# i2c-servo.net
KiCad netlist of a schematic drawn in EAGLE
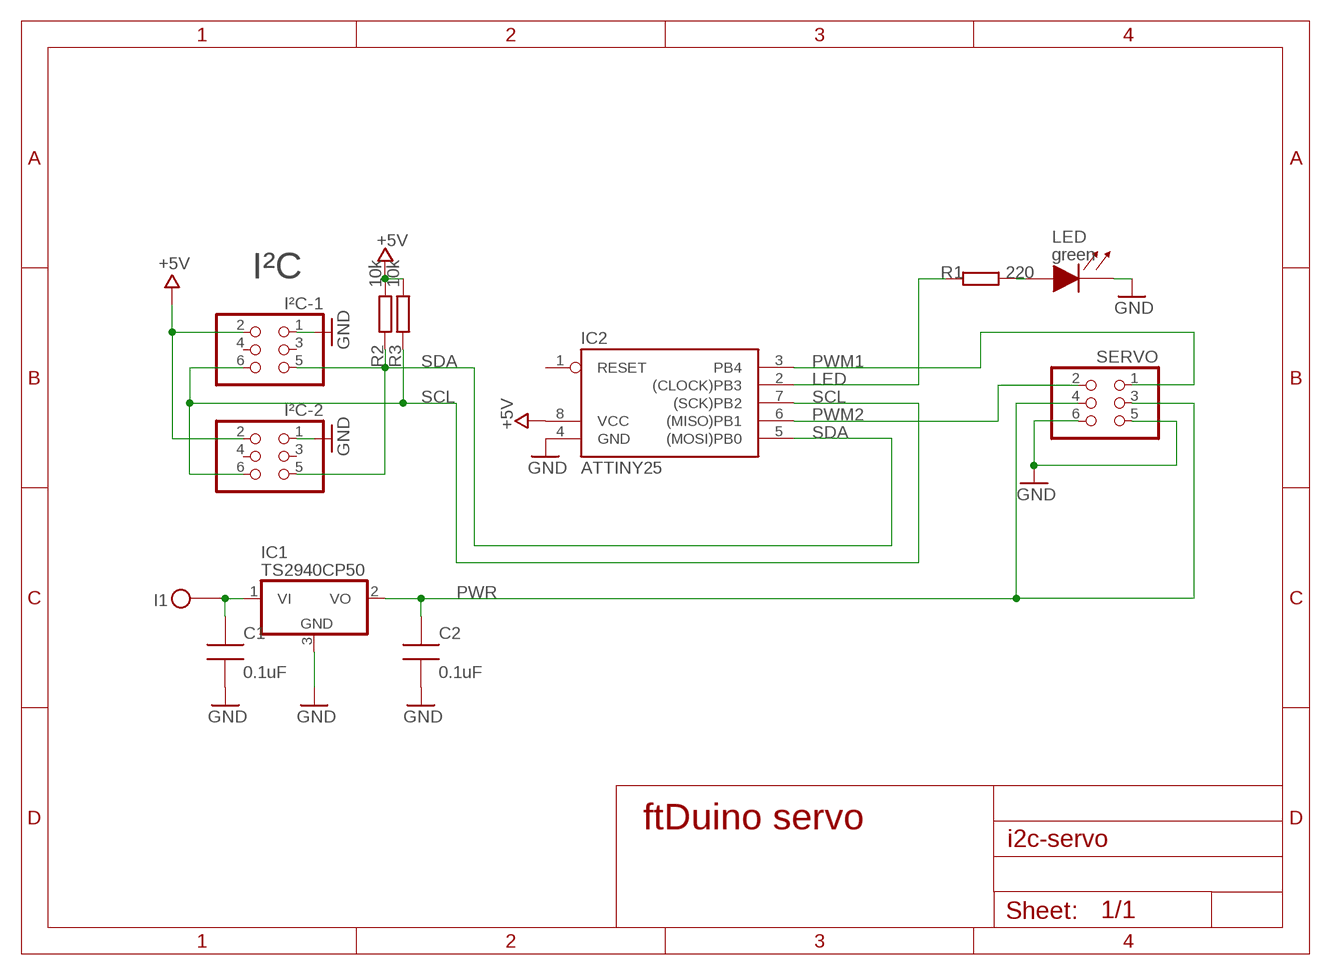
[diagram p0: schematic, sheet 1]

(export (version "E")
  (design (tool "Eeschema 10.0.6"))
  (components
    (comp (ref "C1")
      (value "0.1uF")
      (footprint "eagle-import:CAP0805-NP")
      (libsource (lib "eagle-import") (part "CAP0805-NP"))
    )
    (comp (ref "C2")
      (value "0.1uF")
      (footprint "eagle-import:CAP0805-NP")
      (libsource (lib "eagle-import") (part "CAP0805-NP"))
    )
    (comp (ref "H5")
      (value "I1")
      (footprint "eagle-import:FT-HUELSE")
      (libsource (lib "eagle-import") (part "FT-HUELSE"))
    )
    (comp (ref "IC1")
      (value "TS2940CP50")
      (footprint "eagle-import:TO252")
      (libsource (lib "eagle-import") (part "78DT05"))
    )
    (comp (ref "IC2")
      (value "ATTINY25")
      (footprint "eagle-import:SOIC8")
      (libsource (lib "eagle-import") (part "TINY22S"))
    )
    (comp (ref "I²C-1")
      (value "PINHD-2X3_2.54-SMD")
      (footprint "eagle-import:2X03SMD")
      (libsource (lib "eagle-import") (part "PINHD-2X3_2.54-SMD"))
    )
    (comp (ref "I²C-2")
      (value "PINHD-2X3_2.54-SMD")
      (footprint "eagle-import:2X03SMD")
      (libsource (lib "eagle-import") (part "PINHD-2X3_2.54-SMD"))
    )
    (comp (ref "LED")
      (value "green")
      (footprint "eagle-import:LED0805")
      (libsource (lib "eagle-import") (part "LED0805"))
    )
    (comp (ref "R1")
      (value "220")
      (footprint "eagle-import:M0805")
      (libsource (lib "eagle-import") (part "R-EU_M0805"))
    )
    (comp (ref "R2")
      (value "10k")
      (footprint "eagle-import:M0805")
      (libsource (lib "eagle-import") (part "resistor_R-EU_M0805"))
    )
    (comp (ref "R3")
      (value "10k")
      (footprint "eagle-import:M0805")
      (libsource (lib "eagle-import") (part "resistor_R-EU_M0805"))
    )
    (comp (ref "SERVO")
      (value "PINHD-2X3_2.54-SMD")
      (footprint "eagle-import:2X03SMD")
      (libsource (lib "eagle-import") (part "PINHD-2X3_2.54-SMD"))
    )
  )
  (nets
    (net (code "1") (name "+5V") (class "Default")
      (node (ref "IC2") (pin "8") (pinfunction "VCC_8") (pintype "power_in"))
      (node (ref "I²C-1") (pin "2") (pinfunction "2_2") (pintype "passive"))
      (node (ref "I²C-2") (pin "2") (pinfunction "2_2") (pintype "passive"))
      (node (ref "R2") (pin "2") (pinfunction "2_2") (pintype "passive"))
      (node (ref "R3") (pin "2") (pinfunction "2_2") (pintype "passive"))
    )
    (net (code "2") (name "/LED") (class "Default")
      (node (ref "IC2") (pin "2") (pinfunction "(CLOCK)PB3_2") (pintype "bidirectional"))
      (node (ref "R1") (pin "1") (pinfunction "1_1") (pintype "passive"))
    )
    (net (code "3") (name "/PWM1") (class "Default")
      (node (ref "IC2") (pin "3") (pinfunction "PB4_3") (pintype "bidirectional"))
      (node (ref "SERVO") (pin "1") (pinfunction "1_1") (pintype "passive"))
    )
    (net (code "4") (name "/PWM2") (class "Default")
      (node (ref "IC2") (pin "6") (pinfunction "(MISO)PB1_6") (pintype "bidirectional"))
      (node (ref "SERVO") (pin "2") (pinfunction "2_2") (pintype "passive"))
    )
    (net (code "5") (name "/PWR") (class "Default")
      (node (ref "C2") (pin "1") (pinfunction "1_1") (pintype "passive"))
      (node (ref "IC1") (pin "2") (pinfunction "VO_2") (pintype "passive"))
      (node (ref "SERVO") (pin "3") (pinfunction "3_3") (pintype "passive"))
      (node (ref "SERVO") (pin "4") (pinfunction "4_4") (pintype "passive"))
    )
    (net (code "6") (name "/SCL") (class "Default")
      (node (ref "IC2") (pin "7") (pinfunction "(SCK)PB2_7") (pintype "bidirectional"))
      (node (ref "I²C-1") (pin "6") (pinfunction "6_6") (pintype "passive"))
      (node (ref "I²C-2") (pin "6") (pinfunction "6_6") (pintype "passive"))
      (node (ref "R3") (pin "1") (pinfunction "1_1") (pintype "passive"))
    )
    (net (code "7") (name "/SDA") (class "Default")
      (node (ref "IC2") (pin "5") (pinfunction "(MOSI)PB0_5") (pintype "bidirectional"))
      (node (ref "I²C-1") (pin "5") (pinfunction "5_5") (pintype "passive"))
      (node (ref "I²C-2") (pin "5") (pinfunction "5_5") (pintype "passive"))
      (node (ref "R2") (pin "1") (pinfunction "1_1") (pintype "passive"))
    )
    (net (code "8") (name "GND") (class "Default")
      (node (ref "C1") (pin "2") (pinfunction "2_2") (pintype "passive"))
      (node (ref "C2") (pin "2") (pinfunction "2_2") (pintype "passive"))
      (node (ref "IC1") (pin "3") (pinfunction "GND_3") (pintype "passive"))
      (node (ref "IC2") (pin "4") (pinfunction "GND_4") (pintype "power_in"))
      (node (ref "I²C-1") (pin "1") (pinfunction "1_1") (pintype "passive"))
      (node (ref "I²C-2") (pin "1") (pinfunction "1_1") (pintype "passive"))
      (node (ref "LED") (pin "1") (pinfunction "CA_1") (pintype "passive"))
      (node (ref "SERVO") (pin "5") (pinfunction "5_5") (pintype "passive"))
      (node (ref "SERVO") (pin "6") (pinfunction "6_6") (pintype "passive"))
    )
    (net (code "9") (name "Net-(IC1-VI)") (class "Default")
      (node (ref "C1") (pin "1") (pinfunction "1_1") (pintype "passive"))
      (node (ref "H5") (pin "D1") (pinfunction "D1_D1") (pintype "bidirectional"))
      (node (ref "IC1") (pin "1") (pinfunction "VI_1") (pintype "input"))
    )
    (net (code "10") (name "Net-(LED-AN)") (class "Default")
      (node (ref "LED") (pin "2") (pinfunction "AN_2") (pintype "passive"))
      (node (ref "R1") (pin "2") (pinfunction "2_2") (pintype "passive"))
    )
    (net (code "11") (name "unconnected-(IC2-RESET-Pad1)") (class "Default")
      (node (ref "IC2") (pin "1") (pinfunction "RESET_1") (pintype "input"))
    )
    (net (code "12") (name "unconnected-(I²C-1-Pad3)") (class "Default")
      (node (ref "I²C-1") (pin "3") (pinfunction "3_3") (pintype "passive"))
    )
    (net (code "13") (name "unconnected-(I²C-1-Pad4)") (class "Default")
      (node (ref "I²C-1") (pin "4") (pinfunction "4_4") (pintype "passive"))
    )
    (net (code "14") (name "unconnected-(I²C-2-Pad3)") (class "Default")
      (node (ref "I²C-2") (pin "3") (pinfunction "3_3") (pintype "passive"))
    )
    (net (code "15") (name "unconnected-(I²C-2-Pad4)") (class "Default")
      (node (ref "I²C-2") (pin "4") (pinfunction "4_4") (pintype "passive"))
    )
  )
)
